# Flomio_BLE-NFC_-_LED_Array.net
KiCad netlist of a schematic drawn in Altium Designer
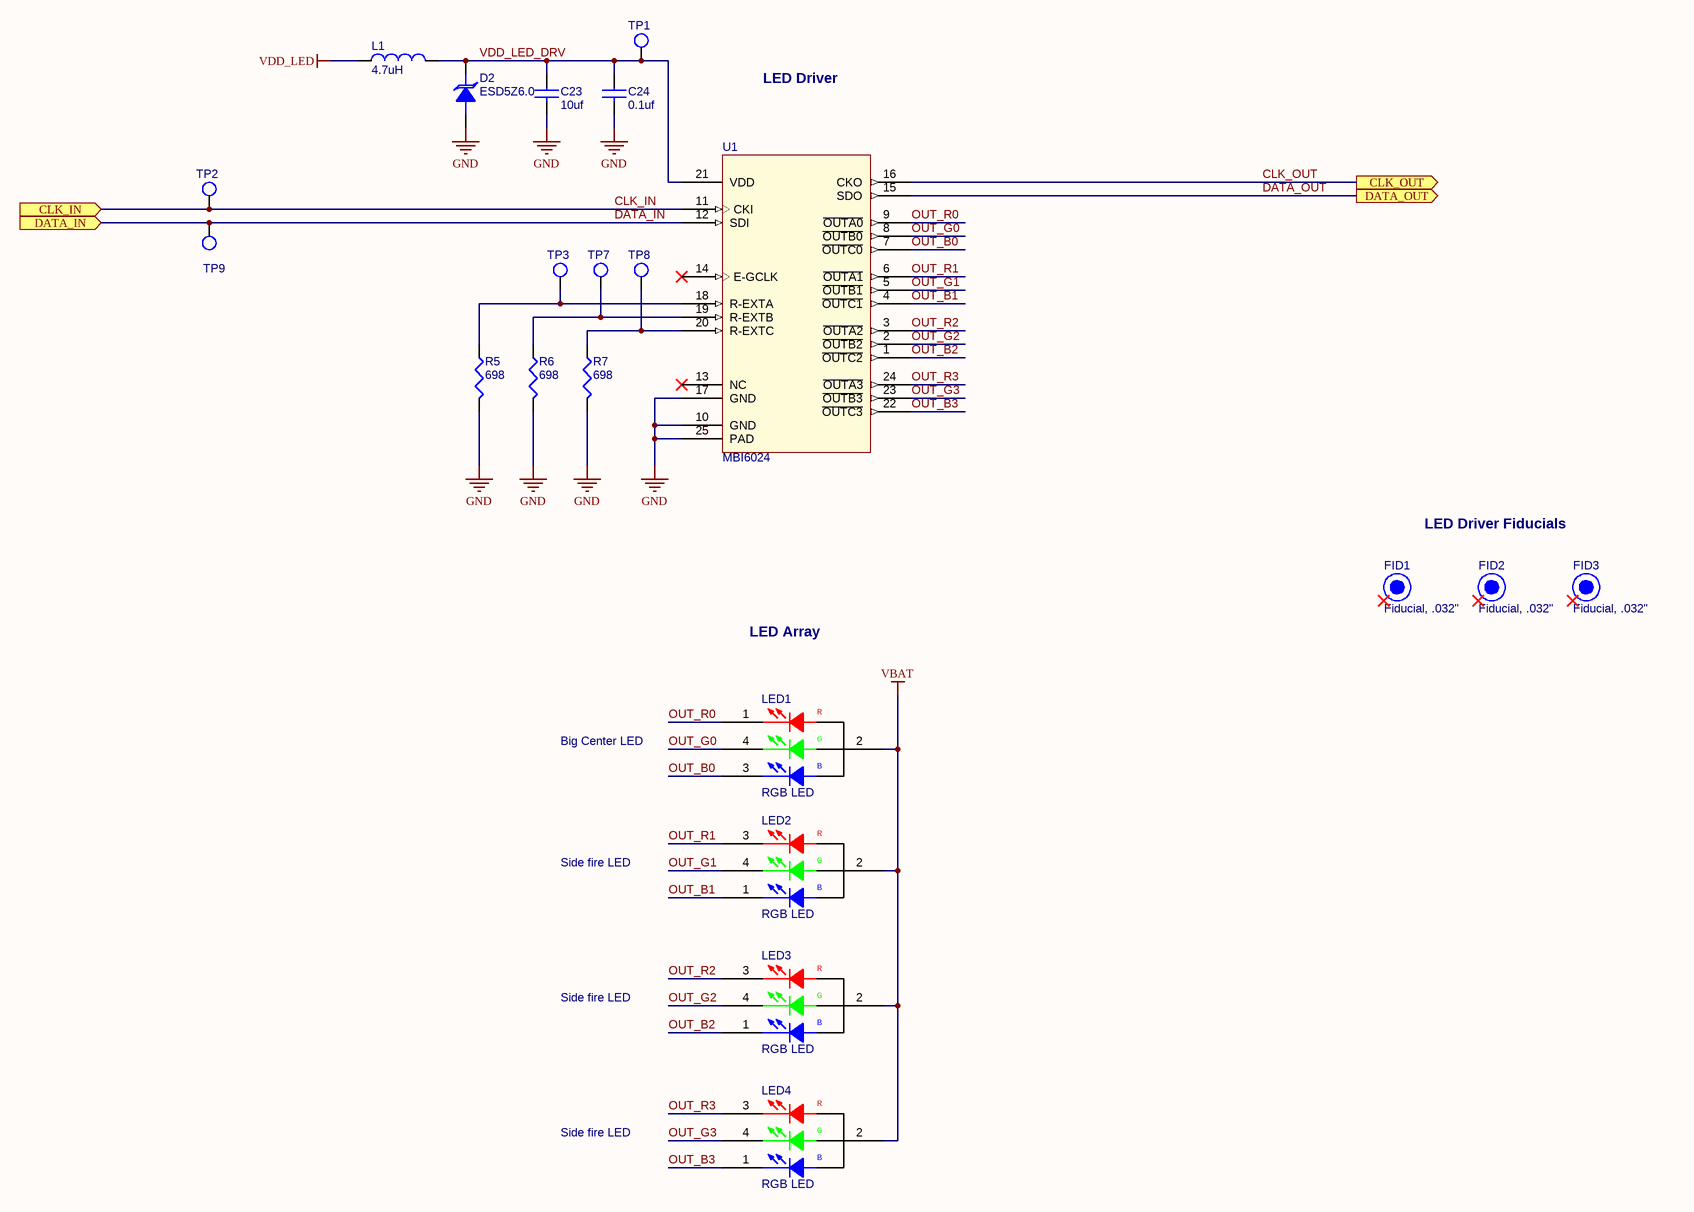
[diagram p0: Flomio BLE-NFC - LED Array.SchDoc]

(export (version "E")
  (design (tool "Eeschema 10.0.6"))
  (components
    (comp (ref "C23")
      (value "10uf")
      (footprint "SM/C_0603")
      (description "Cap, 0603, 10uf, 6.3V, 20%,")
      (fields (field (name "PART NUMBER") "GRM188R60J106ME47") (field (name "TOLERANCE") "20%"))
      (libsource (lib "Anidea") (part "CAP NP"))
    )
    (comp (ref "C24")
      (value "0.1uf")
      (footprint "SM/C_0402")
      (description "Cap, 0402, 0.1uf, 16V, 10%")
      (fields (field (name "PART NUMBER") "GRM155R71C104KA88") (field (name "TOLERANCE") "10%"))
      (libsource (lib "Anidea") (part "CAP NP"))
    )
    (comp (ref "D2")
      (value "ESD5Z6.0")
      (footprint "SOD-523")
      (description "TVS, ESD, 6.0V, 30KV Pk, Unidirectional, SMT")
      (fields (field (name "PART NUMBER") "ESD5Z6.0T1G") (field (name "VOLTAGE") "6.0V"))
      (libsource (lib "Anidea") (part "DIODE TS"))
    )
    (comp (ref "FID1")
      (value "Fiducial, .032\"")
      (footprint "FID32")
      (description "Fiducual, .032\" Pad")
      (fields (field (name "PART NUMBER") "FID32"))
      (libsource (lib "Anidea") (part "FIDUCIAL"))
    )
    (comp (ref "FID2")
      (value "Fiducial, .032\"")
      (footprint "FID32")
      (description "Fiducual, .032\" Pad")
      (fields (field (name "PART NUMBER") "FID32"))
      (libsource (lib "Anidea") (part "FIDUCIAL"))
    )
    (comp (ref "FID3")
      (value "Fiducial, .032\"")
      (footprint "FID32")
      (description "Fiducual, .032\" Pad")
      (fields (field (name "PART NUMBER") "FID32"))
      (libsource (lib "Anidea") (part "FIDUCIAL"))
    )
    (comp (ref "L1")
      (value "4.7uH")
      (footprint "SM/I_0805")
      (description "Inductor, 4.7uH, 0805")
      (fields (field (name "PART NUMBER") "LQG21C4R7N00T1") (field (name "MFG") "Murata"))
      (libsource (lib "Anidea") (part "INDUCTOR"))
    )
    (comp (ref "LED1")
      (value "RGB LED")
      (footprint "LED/PLCC4;LED/PLCC4/NOSLK")
      (description "Diode, Led, RGB, PLCC4")
      (fields
        (field (name "PART NUMBER") "CLVBA-FKA")
        (field (name "MFG PART NUMBER") "CLVBA-FKA-CAEDH8BBB7a36")
      )
      (libsource (lib "Anidea") (part "CLVBA-FKA"))
    )
    (comp (ref "LED2")
      (value "RGB LED")
      (footprint "LED/AVAGO/HSMF-C115")
      (description "Diode, Led, RGB, Side looking")
      (fields (field (name "PART NUMBER") "HSMF-C115") (field (name "MFG") "Avago"))
      (libsource (lib "Anidea") (part "LED/HSMF"))
    )
    (comp (ref "LED3")
      (value "RGB LED")
      (footprint "LED/AVAGO/HSMF-C115")
      (description "Diode, Led, RGB, Side looking")
      (fields (field (name "PART NUMBER") "HSMF-C115") (field (name "MFG") "Avago"))
      (libsource (lib "Anidea") (part "LED/HSMF"))
    )
    (comp (ref "LED4")
      (value "RGB LED")
      (footprint "LED/AVAGO/HSMF-C115")
      (description "Diode, Led, RGB, Side looking")
      (fields (field (name "PART NUMBER") "HSMF-C115") (field (name "MFG") "Avago"))
      (libsource (lib "Anidea") (part "LED/HSMF"))
    )
    (comp (ref "R5")
      (value "698")
      (footprint "SM/R_0402")
      (description "Resistor, 0402, 698 Ohm 1%")
      (fields (field (name "PART NUMBER") "CRCW0402698RFK") (field (name "TOLERANCE") "1%"))
      (libsource (lib "Anidea") (part "R"))
    )
    (comp (ref "R6")
      (value "698")
      (footprint "SM/R_0402")
      (description "Resistor, 0402, 698 Ohm 1%")
      (fields (field (name "PART NUMBER") "CRCW0402698RFK") (field (name "TOLERANCE") "1%"))
      (libsource (lib "Anidea") (part "R"))
    )
    (comp (ref "R7")
      (value "698")
      (footprint "SM/R_0402")
      (description "Resistor, 0402, 698 Ohm 1%")
      (fields (field (name "PART NUMBER") "CRCW0402698RFK") (field (name "TOLERANCE") "1%"))
      (libsource (lib "Anidea") (part "R"))
    )
    (comp (ref "TP1")
      (value "TP")
      (footprint "VIA18")
      (description "Testpoint, 18mil Hole, No part, just via")
      (fields (field (name "PART NUMBER") "TP18"))
      (libsource (lib "Anidea") (part "T POINT R"))
    )
    (comp (ref "TP2")
      (value "TP")
      (footprint "VIA18")
      (description "Testpoint, 18mil Hole, No part, just via")
      (fields (field (name "PART NUMBER") "TP18"))
      (libsource (lib "Anidea") (part "T POINT R"))
    )
    (comp (ref "TP3")
      (value "TP")
      (footprint "VIA18")
      (description "Testpoint, 18mil Hole, No part, just via")
      (fields (field (name "PART NUMBER") "TP18"))
      (libsource (lib "Anidea") (part "T POINT R"))
    )
    (comp (ref "TP7")
      (value "TP")
      (footprint "VIA18")
      (description "Testpoint, 18mil Hole, No part, just via")
      (fields (field (name "PART NUMBER") "TP18"))
      (libsource (lib "Anidea") (part "T POINT R"))
    )
    (comp (ref "TP8")
      (value "TP")
      (footprint "VIA18")
      (description "Testpoint, 18mil Hole, No part, just via")
      (fields (field (name "PART NUMBER") "TP18"))
      (libsource (lib "Anidea") (part "T POINT R"))
    )
    (comp (ref "TP9")
      (value "TP")
      (footprint "VIA18")
      (description "Testpoint, 18mil Hole, No part, just via")
      (fields (field (name "PART NUMBER") "TP18"))
      (libsource (lib "Anidea") (part "T POINT R"))
    )
    (comp (ref "U1")
      (value "MBI6024")
      (footprint "QFN50P400X400X80-24N")
      (description "IC, Driver, 3x4 Led Driver, QFN24")
      (fields (field (name "PART NUMBER") "MBI6024GFN") (field (name "VOLTAGE") "5V"))
      (libsource (lib "Anidea") (part "MBI6024"))
    )
  )
  (nets
    (net (code "1") (name "/CLK_IN") (class "Default")
      (node (ref "TP2") (pin "1") (pinfunction "TP_1") (pintype "passive"))
      (node (ref "U1") (pin "11") (pinfunction "CKI_11") (pintype "input"))
    )
    (net (code "2") (name "/CLK_OUT") (class "Default")
      (node (ref "U1") (pin "16") (pinfunction "CKO_16") (pintype "output"))
    )
    (net (code "3") (name "/DATA_IN") (class "Default")
      (node (ref "TP9") (pin "1") (pinfunction "TP_1") (pintype "passive"))
      (node (ref "U1") (pin "12") (pinfunction "SDI_12") (pintype "input"))
    )
    (net (code "4") (name "/DATA_OUT") (class "Default")
      (node (ref "U1") (pin "15") (pinfunction "SDO_15") (pintype "output"))
    )
    (net (code "5") (name "/OUT_B0") (class "Default")
      (node (ref "LED1") (pin "3") (pinfunction "BLUEK_3") (pintype "passive"))
      (node (ref "U1") (pin "7") (pinfunction "~{OUTC0}_7") (pintype "output"))
    )
    (net (code "6") (name "/OUT_B1") (class "Default")
      (node (ref "LED2") (pin "1") (pinfunction "BLUEK_1") (pintype "passive"))
      (node (ref "U1") (pin "4") (pinfunction "~{OUTC1}_4") (pintype "output"))
    )
    (net (code "7") (name "/OUT_B2") (class "Default")
      (node (ref "LED3") (pin "1") (pinfunction "BLUEK_1") (pintype "passive"))
      (node (ref "U1") (pin "1") (pinfunction "~{OUTC2}_1") (pintype "output"))
    )
    (net (code "8") (name "/OUT_B3") (class "Default")
      (node (ref "LED4") (pin "1") (pinfunction "BLUEK_1") (pintype "passive"))
      (node (ref "U1") (pin "22") (pinfunction "~{OUTC3}_22") (pintype "output"))
    )
    (net (code "9") (name "/OUT_G0") (class "Default")
      (node (ref "LED1") (pin "4") (pinfunction "GREENK_4") (pintype "passive"))
      (node (ref "U1") (pin "8") (pinfunction "~{OUTB0}_8") (pintype "output"))
    )
    (net (code "10") (name "/OUT_G1") (class "Default")
      (node (ref "LED2") (pin "4") (pinfunction "GREENK_4") (pintype "passive"))
      (node (ref "U1") (pin "5") (pinfunction "~{OUTB1}_5") (pintype "output"))
    )
    (net (code "11") (name "/OUT_G2") (class "Default")
      (node (ref "LED3") (pin "4") (pinfunction "GREENK_4") (pintype "passive"))
      (node (ref "U1") (pin "2") (pinfunction "~{OUTB2}_2") (pintype "output"))
    )
    (net (code "12") (name "/OUT_G3") (class "Default")
      (node (ref "LED4") (pin "4") (pinfunction "GREENK_4") (pintype "passive"))
      (node (ref "U1") (pin "23") (pinfunction "~{OUTB3}_23") (pintype "output"))
    )
    (net (code "13") (name "/OUT_R0") (class "Default")
      (node (ref "LED1") (pin "1") (pinfunction "REDK_1") (pintype "passive"))
      (node (ref "U1") (pin "9") (pinfunction "~{OUTA0}_9") (pintype "output"))
    )
    (net (code "14") (name "/OUT_R1") (class "Default")
      (node (ref "LED2") (pin "3") (pinfunction "REDK_3") (pintype "passive"))
      (node (ref "U1") (pin "6") (pinfunction "~{OUTA1}_6") (pintype "output"))
    )
    (net (code "15") (name "/OUT_R2") (class "Default")
      (node (ref "LED3") (pin "3") (pinfunction "REDK_3") (pintype "passive"))
      (node (ref "U1") (pin "3") (pinfunction "~{OUTA2}_3") (pintype "output"))
    )
    (net (code "16") (name "/OUT_R3") (class "Default")
      (node (ref "LED4") (pin "3") (pinfunction "REDK_3") (pintype "passive"))
      (node (ref "U1") (pin "24") (pinfunction "~{OUTA3}_24") (pintype "output"))
    )
    (net (code "17") (name "/VDD_LED_DRV") (class "Default")
      (node (ref "C23") (pin "1") (pinfunction "1_1") (pintype "passive"))
      (node (ref "C24") (pin "1") (pinfunction "1_1") (pintype "passive"))
      (node (ref "D2") (pin "2") (pinfunction "CATHODE_2") (pintype "passive"))
      (node (ref "L1") (pin "2") (pinfunction "2_2") (pintype "passive"))
      (node (ref "TP1") (pin "1") (pinfunction "TP_1") (pintype "passive"))
      (node (ref "U1") (pin "21") (pinfunction "VDD_21") (pintype "power_in"))
    )
    (net (code "18") (name "GND") (class "Default")
      (node (ref "C23") (pin "2") (pinfunction "2_2") (pintype "passive"))
      (node (ref "C24") (pin "2") (pinfunction "2_2") (pintype "passive"))
      (node (ref "D2") (pin "1") (pinfunction "ANODE_1") (pintype "passive"))
      (node (ref "R5") (pin "2") (pinfunction "2_2") (pintype "passive"))
      (node (ref "R6") (pin "2") (pinfunction "2_2") (pintype "passive"))
      (node (ref "R7") (pin "2") (pinfunction "2_2") (pintype "passive"))
      (node (ref "U1") (pin "10") (pinfunction "GND_10") (pintype "passive"))
      (node (ref "U1") (pin "17") (pinfunction "GND_17") (pintype "passive"))
      (node (ref "U1") (pin "25") (pinfunction "PAD_25") (pintype "passive"))
    )
    (net (code "19") (name "Net-(TP3-TP)") (class "Default")
      (node (ref "R5") (pin "1") (pinfunction "1_1") (pintype "passive"))
      (node (ref "TP3") (pin "1") (pinfunction "TP_1") (pintype "passive"))
      (node (ref "U1") (pin "18") (pinfunction "R-EXTA_18") (pintype "input"))
    )
    (net (code "20") (name "Net-(TP7-TP)") (class "Default")
      (node (ref "R6") (pin "1") (pinfunction "1_1") (pintype "passive"))
      (node (ref "TP7") (pin "1") (pinfunction "TP_1") (pintype "passive"))
      (node (ref "U1") (pin "19") (pinfunction "R-EXTB_19") (pintype "input"))
    )
    (net (code "21") (name "Net-(TP8-TP)") (class "Default")
      (node (ref "R7") (pin "1") (pinfunction "1_1") (pintype "passive"))
      (node (ref "TP8") (pin "1") (pinfunction "TP_1") (pintype "passive"))
      (node (ref "U1") (pin "20") (pinfunction "R-EXTC_20") (pintype "input"))
    )
    (net (code "22") (name "VBAT") (class "Default")
      (node (ref "LED1") (pin "2") (pinfunction "ANODDE_2") (pintype "passive"))
      (node (ref "LED2") (pin "2") (pinfunction "ANODDE_2") (pintype "passive"))
      (node (ref "LED3") (pin "2") (pinfunction "ANODDE_2") (pintype "passive"))
      (node (ref "LED4") (pin "2") (pinfunction "ANODDE_2") (pintype "passive"))
    )
    (net (code "23") (name "VDD_LED") (class "Default")
      (node (ref "L1") (pin "1") (pinfunction "1_1") (pintype "passive"))
    )
    (net (code "24") (name "unconnected-(FID1-Pad1)") (class "Default")
      (node (ref "FID1") (pin "1") (pinfunction "1_1") (pintype "passive+no_connect"))
    )
    (net (code "25") (name "unconnected-(FID2-Pad1)") (class "Default")
      (node (ref "FID2") (pin "1") (pinfunction "1_1") (pintype "passive+no_connect"))
    )
    (net (code "26") (name "unconnected-(FID3-Pad1)") (class "Default")
      (node (ref "FID3") (pin "1") (pinfunction "1_1") (pintype "passive+no_connect"))
    )
    (net (code "27") (name "unconnected-(U1-E-GCLK-Pad14)") (class "Default")
      (node (ref "U1") (pin "14") (pinfunction "E-GCLK_14") (pintype "input+no_connect"))
    )
    (net (code "28") (name "unconnected-(U1-NC-Pad13)") (class "Default")
      (node (ref "U1") (pin "13") (pinfunction "NC_13") (pintype "passive+no_connect"))
    )
  )
)
